# Audio.net
KiCad netlist of a schematic drawn in Altium Designer
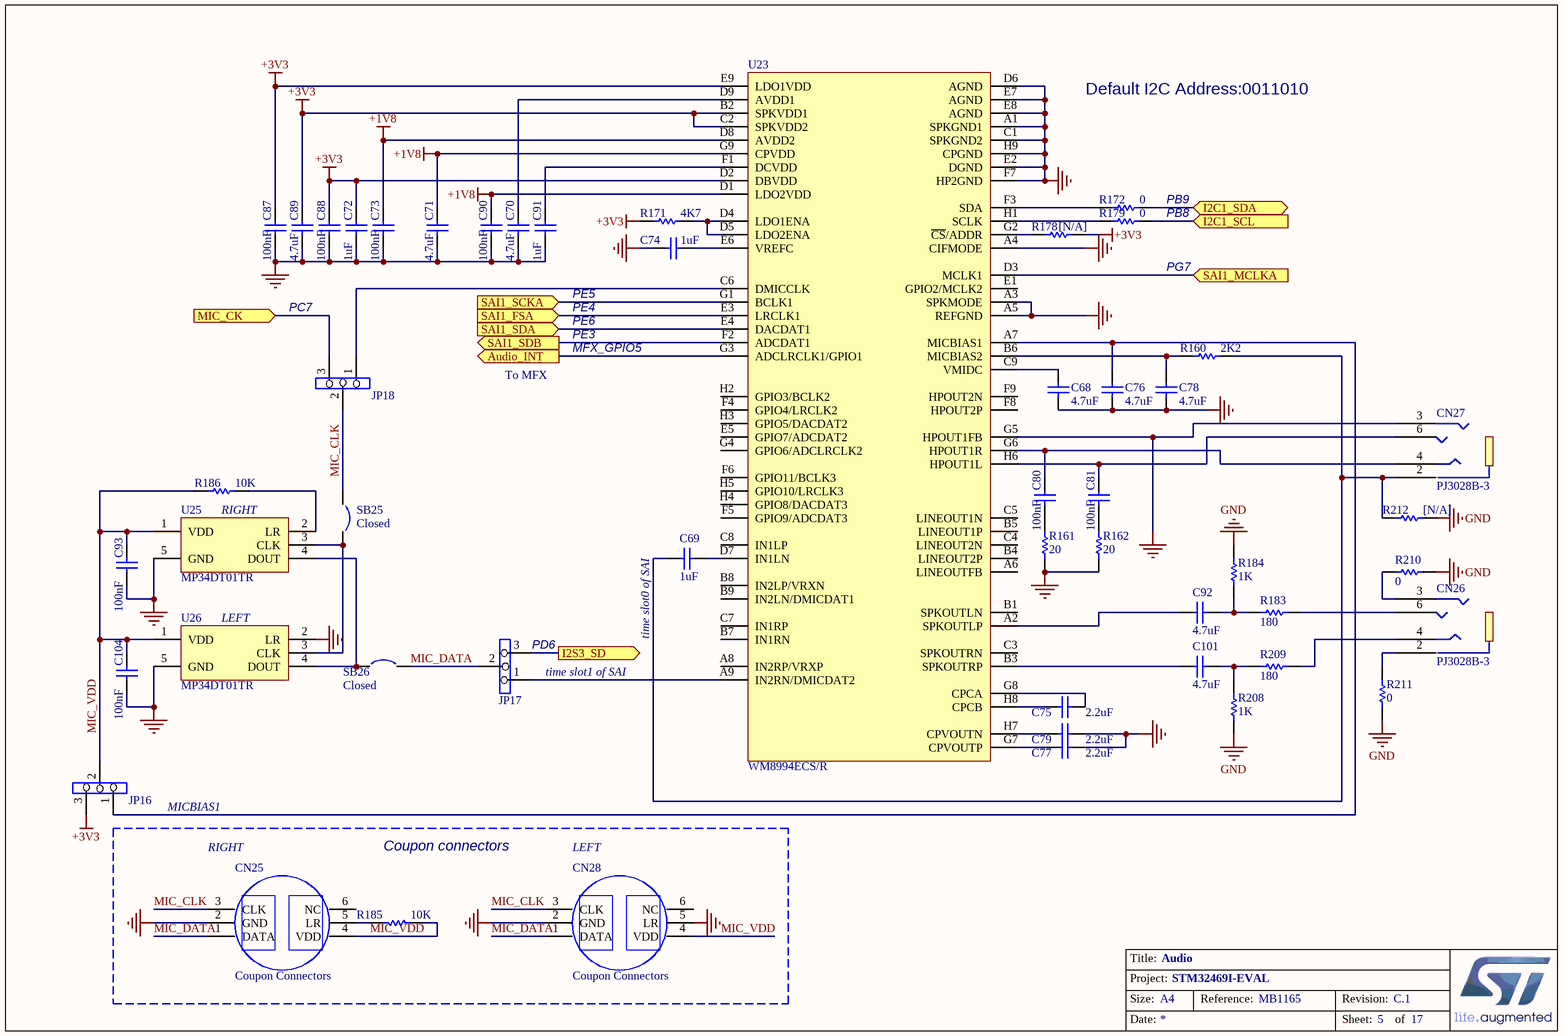
[diagram p0: Audio.SchDoc]

(export (version "E")
  (design (tool "Eeschema 10.0.6"))
  (components
    (comp (ref "C68")
      (value "4.7uF")
      (footprint "0603C")
      (description "Capacitor")
      (fields (field (name "PUBLISHER") "Altium Limited"))
      (libsource (lib "Miscellaneous Devices") (part "Cap"))
    )
    (comp (ref "C69")
      (value "1uF")
      (footprint "0603C")
      (description "Capacitor")
      (fields (field (name "PUBLISHER") "Altium Limited"))
      (libsource (lib "Miscellaneous Devices") (part "CAP"))
    )
    (comp (ref "C70")
      (value "4.7uF")
      (footprint "0603C")
      (description "Capacitor")
      (fields (field (name "PUBLISHER") "Altium Limited"))
      (libsource (lib "Miscellaneous Devices") (part "Cap"))
    )
    (comp (ref "C71")
      (value "4.7uF")
      (footprint "0603C")
      (description "Capacitor")
      (fields (field (name "PUBLISHER") "Altium Limited"))
      (libsource (lib "Miscellaneous Devices") (part "Cap"))
    )
    (comp (ref "C72")
      (value "1uF")
      (footprint "0603C")
      (description "Capacitor")
      (fields (field (name "PUBLISHER") "Altium Limited"))
      (libsource (lib "Miscellaneous Devices") (part "CAP"))
    )
    (comp (ref "C73")
      (value "100nF")
      (footprint "0603C")
      (description "Capacitor")
      (fields (field (name "PUBLISHER") "Altium Limited"))
      (libsource (lib "Miscellaneous Devices") (part "Cap"))
    )
    (comp (ref "C74")
      (value "1uF")
      (footprint "0603C")
      (description "Capacitor")
      (fields (field (name "PUBLISHER") "Altium Limited"))
      (libsource (lib "Miscellaneous Devices") (part "CAP"))
    )
    (comp (ref "C75")
      (value "2.2uF")
      (footprint "0603C")
      (description "Capacitor")
      (fields (field (name "PUBLISHER") "Altium Limited"))
      (libsource (lib "Miscellaneous Devices") (part "CAP"))
    )
    (comp (ref "C76")
      (value "4.7uF")
      (footprint "0603C")
      (description "Capacitor")
      (fields (field (name "PUBLISHER") "Altium Limited"))
      (libsource (lib "Miscellaneous Devices") (part "Cap"))
    )
    (comp (ref "C77")
      (value "2.2uF")
      (footprint "0603C")
      (description "Capacitor")
      (fields (field (name "PUBLISHER") "Altium Limited"))
      (libsource (lib "Miscellaneous Devices") (part "CAP"))
    )
    (comp (ref "C78")
      (value "4.7uF")
      (footprint "0603C")
      (description "Capacitor")
      (fields (field (name "PUBLISHER") "Altium Limited"))
      (libsource (lib "Miscellaneous Devices") (part "Cap"))
    )
    (comp (ref "C79")
      (value "2.2uF")
      (footprint "0603C")
      (description "Capacitor")
      (fields (field (name "PUBLISHER") "Altium Limited"))
      (libsource (lib "Miscellaneous Devices") (part "CAP"))
    )
    (comp (ref "C80")
      (value "100nF")
      (footprint "0603C")
      (description "Capacitor")
      (fields (field (name "PUBLISHER") "Altium Limited"))
      (libsource (lib "Miscellaneous Devices") (part "Cap"))
    )
    (comp (ref "C81")
      (value "100nF")
      (footprint "0603C")
      (description "Capacitor")
      (fields (field (name "PUBLISHER") "Altium Limited"))
      (libsource (lib "Miscellaneous Devices") (part "Cap"))
    )
    (comp (ref "C87")
      (value "100nF")
      (footprint "0603C")
      (description "Capacitor")
      (fields (field (name "PUBLISHER") "Altium Limited"))
      (libsource (lib "Miscellaneous Devices") (part "Cap"))
    )
    (comp (ref "C88")
      (value "100nF")
      (footprint "0603C")
      (description "Capacitor")
      (fields (field (name "PUBLISHER") "Altium Limited"))
      (libsource (lib "Miscellaneous Devices") (part "Cap"))
    )
    (comp (ref "C89")
      (value "4.7uF")
      (footprint "0603C")
      (description "Capacitor")
      (fields (field (name "PUBLISHER") "Altium Limited"))
      (libsource (lib "Miscellaneous Devices") (part "Cap"))
    )
    (comp (ref "C90")
      (value "100nF")
      (footprint "0603C")
      (description "Capacitor")
      (fields (field (name "PUBLISHER") "Altium Limited"))
      (libsource (lib "Miscellaneous Devices") (part "Cap"))
    )
    (comp (ref "C91")
      (value "1uF")
      (footprint "0603C")
      (description "Capacitor")
      (fields (field (name "PUBLISHER") "Altium Limited"))
      (libsource (lib "Miscellaneous Devices") (part "CAP"))
    )
    (comp (ref "C92")
      (value "4.7uF")
      (footprint "0603C")
      (description "Capacitor")
      (fields (field (name "PUBLISHER") "Altium Limited"))
      (libsource (lib "Miscellaneous Devices") (part "Cap"))
    )
    (comp (ref "C93")
      (value "100nF")
      (footprint "0603C")
      (description "Capacitor")
      (fields (field (name "PUBLISHER") "Altium Limited"))
      (libsource (lib "Miscellaneous Devices") (part "Cap"))
    )
    (comp (ref "C101")
      (value "4.7uF")
      (footprint "0603C")
      (description "Capacitor")
      (fields (field (name "PUBLISHER") "Altium Limited"))
      (libsource (lib "Miscellaneous Devices") (part "Cap"))
    )
    (comp (ref "C104")
      (value "100nF")
      (footprint "0603C")
      (description "Capacitor")
      (fields (field (name "PUBLISHER") "Altium Limited"))
      (libsource (lib "Miscellaneous Devices") (part "Cap"))
    )
    (comp (ref "CN25")
      (value "Coupon Connectors")
      (footprint "Coupon")
      (description "Header, 3-Pin, Single row")
      (fields (field (name "PUBLISHER") "Altium Limited"))
      (libsource (lib "MB1167") (part "Coupon Connectors"))
    )
    (comp (ref "CN26") (value "PJ3028B-3") (footprint "PJ3028B") (libsource (lib "MB786") (part "PJ3028B-3")))
    (comp (ref "CN27") (value "PJ3028B-3") (footprint "PJ3028B") (libsource (lib "MB786") (part "PJ3028B-3")))
    (comp (ref "CN28")
      (value "Coupon Connectors")
      (footprint "Coupon")
      (description "Header, 3-Pin, Single row")
      (fields (field (name "PUBLISHER") "Altium Limited"))
      (libsource (lib "MB1167") (part "Coupon Connectors"))
    )
    (comp (ref "JP16") (value "~") (footprint "SIP3") (libsource (lib "STR910_SCHLIB") (part "Jumper3")))
    (comp (ref "JP17") (value "~") (footprint "SIP3") (libsource (lib "STR910_SCHLIB") (part "Jumper3")))
    (comp (ref "JP18") (value "~") (footprint "SIP3") (libsource (lib "STR910_SCHLIB") (part "Jumper3")))
    (comp (ref "R160")
      (value "2K2")
      (footprint "0603R")
      (description "Resistor")
      (fields (field (name "PUBLISHER") "Altium Limited"))
      (libsource (lib "Miscellaneous Devices") (part "Res1"))
    )
    (comp (ref "R161")
      (value "20")
      (footprint "0603R")
      (description "Resistor")
      (fields (field (name "PUBLISHER") "Altium Limited"))
      (libsource (lib "Miscellaneous Devices") (part "Res1"))
    )
    (comp (ref "R162")
      (value "20")
      (footprint "0603R")
      (description "Resistor")
      (fields (field (name "PUBLISHER") "Altium Limited"))
      (libsource (lib "Miscellaneous Devices") (part "Res1"))
    )
    (comp (ref "R171")
      (value "4K7")
      (footprint "0603R")
      (description "Resistor")
      (fields (field (name "PUBLISHER") "Altium Limited"))
      (libsource (lib "Miscellaneous Devices") (part "Res1"))
    )
    (comp (ref "R172")
      (value "0")
      (footprint "0603R")
      (description "Resistor")
      (fields (field (name "PUBLISHER") "Altium Limited"))
      (libsource (lib "Miscellaneous Devices") (part "Res1"))
    )
    (comp (ref "R178")
      (value "[N/A]")
      (footprint "0603R")
      (description "Resistor")
      (fields (field (name "PUBLISHER") "Altium Limited"))
      (libsource (lib "Miscellaneous Devices") (part "Res1"))
    )
    (comp (ref "R179")
      (value "0")
      (footprint "0603R")
      (description "Resistor")
      (fields (field (name "PUBLISHER") "Altium Limited"))
      (libsource (lib "Miscellaneous Devices") (part "Res1"))
    )
    (comp (ref "R183")
      (value "180")
      (footprint "0402R")
      (description "Resistor")
      (fields (field (name "PUBLISHER") "Altium Limited"))
      (libsource (lib "Miscellaneous Devices") (part "Res1"))
    )
    (comp (ref "R184")
      (value "1K")
      (footprint "0402R")
      (description "Resistor")
      (fields (field (name "PUBLISHER") "Altium Limited"))
      (libsource (lib "Miscellaneous Devices") (part "Res1"))
    )
    (comp (ref "R185")
      (value "10K")
      (footprint "0603R")
      (description "Resistor")
      (fields (field (name "PUBLISHER") "Altium Limited"))
      (libsource (lib "Miscellaneous Devices") (part "Res1"))
    )
    (comp (ref "R186")
      (value "10K")
      (footprint "0603R")
      (description "Resistor")
      (fields (field (name "PUBLISHER") "Altium Limited"))
      (libsource (lib "Miscellaneous Devices") (part "Res1"))
    )
    (comp (ref "R208")
      (value "1K")
      (footprint "0402R")
      (description "Resistor")
      (fields (field (name "PUBLISHER") "Altium Limited"))
      (libsource (lib "Miscellaneous Devices") (part "Res1"))
    )
    (comp (ref "R209")
      (value "180")
      (footprint "0402R")
      (description "Resistor")
      (fields (field (name "PUBLISHER") "Altium Limited"))
      (libsource (lib "Miscellaneous Devices") (part "Res1"))
    )
    (comp (ref "R210")
      (value "0")
      (footprint "0603R")
      (description "Resistor")
      (fields (field (name "PUBLISHER") "Altium Limited"))
      (libsource (lib "Miscellaneous Devices") (part "Res1"))
    )
    (comp (ref "R211")
      (value "0")
      (footprint "0603R")
      (description "Resistor")
      (fields (field (name "PUBLISHER") "Altium Limited"))
      (libsource (lib "Miscellaneous Devices") (part "Res1"))
    )
    (comp (ref "R212")
      (value "[N/A]")
      (footprint "0603R")
      (description "Resistor")
      (fields (field (name "PUBLISHER") "Altium Limited"))
      (libsource (lib "Miscellaneous Devices") (part "Res1"))
    )
    (comp (ref "SB25")
      (value "Closed")
      (footprint "SB_0603")
      (description "Circuit Breaker")
      (fields (field (name "PUBLISHER") "Altium Limited"))
      (libsource (lib "MB1165") (part "Circuit Breaker_close"))
    )
    (comp (ref "SB26")
      (value "Closed")
      (footprint "SB_0603")
      (description "Circuit Breaker")
      (fields (field (name "PUBLISHER") "Altium Limited"))
      (libsource (lib "MB1165") (part "Circuit Breaker_close"))
    )
    (comp (ref "U23")
      (value "WM8994ECS/R")
      (footprint "BGA72_0R5_4R5X4")
      (libsource (lib "mb1045") (part "WM8994ECS/R"))
    )
    (comp (ref "U25")
      (value "MP34DT01TR")
      (footprint "MP34DT01TR")
      (description "MEMS audio sensor")
      (fields (field (name "PUBLISHER") "Altium Limited"))
      (libsource (lib "mb1045") (part "MP34DT01TR"))
    )
    (comp (ref "U26")
      (value "MP34DT01TR")
      (footprint "MP34DT01TR")
      (description "MEMS audio sensor")
      (fields (field (name "PUBLISHER") "Altium Limited"))
      (libsource (lib "mb1045") (part "MP34DT01TR"))
    )
  )
  (nets
    (net (code "1") (name "+1V8") (class "Default")
      (node (ref "C71") (pin "1") (pinfunction "1_1") (pintype "passive"))
      (node (ref "C73") (pin "1") (pinfunction "1_1") (pintype "passive"))
      (node (ref "C90") (pin "1") (pinfunction "1_1") (pintype "passive"))
      (node (ref "U23") (pin "D1") (pinfunction "LDO2VDD_D1") (pintype "passive"))
      (node (ref "U23") (pin "D8") (pinfunction "AVDD2_D8") (pintype "passive"))
      (node (ref "U23") (pin "G9") (pinfunction "CPVDD_G9") (pintype "passive"))
    )
    (net (code "2") (name "+3V3") (class "Default")
      (node (ref "C72") (pin "1") (pinfunction "1_1") (pintype "passive"))
      (node (ref "C87") (pin "1") (pinfunction "1_1") (pintype "passive"))
      (node (ref "C88") (pin "1") (pinfunction "1_1") (pintype "passive"))
      (node (ref "C89") (pin "1") (pinfunction "1_1") (pintype "passive"))
      (node (ref "JP16") (pin "3") (pintype "passive"))
      (node (ref "R171") (pin "2") (pinfunction "2_2") (pintype "passive"))
      (node (ref "R178") (pin "1") (pinfunction "1_1") (pintype "passive"))
      (node (ref "U23") (pin "B2") (pinfunction "SPKVDD1_B2") (pintype "passive"))
      (node (ref "U23") (pin "C2") (pinfunction "SPKVDD2_C2") (pintype "passive"))
      (node (ref "U23") (pin "D2") (pinfunction "DBVDD_D2") (pintype "passive"))
      (node (ref "U23") (pin "E9") (pinfunction "LDO1VDD_E9") (pintype "passive"))
    )
    (net (code "3") (name "/Audio_INT") (class "Default")
      (node (ref "U23") (pin "G3") (pinfunction "ADCLRCLK1/GPIO1_G3") (pintype "passive"))
    )
    (net (code "4") (name "/I2C1_SCL") (class "Default")
      (node (ref "R179") (pin "1") (pinfunction "1_1") (pintype "passive"))
    )
    (net (code "5") (name "/I2C1_SDA") (class "Default")
      (node (ref "R172") (pin "1") (pinfunction "1_1") (pintype "passive"))
    )
    (net (code "6") (name "/I2S3_SD") (class "Default") (node (ref "JP17") (pin "3") (pintype "passive")))
    (net (code "7") (name "/MIC_CK") (class "Default") (node (ref "JP18") (pin "3") (pintype "passive")))
    (net (code "8") (name "/MIC_CLK") (class "Default")
      (node (ref "CN25") (pin "3") (pinfunction "CLK_3") (pintype "passive"))
      (node (ref "CN28") (pin "3") (pinfunction "CLK_3") (pintype "passive"))
      (node (ref "JP18") (pin "2") (pintype "passive"))
      (node (ref "SB25") (pin "1") (pinfunction "1_1") (pintype "passive"))
    )
    (net (code "9") (name "/MIC_DATA") (class "Default")
      (node (ref "CN25") (pin "1") (pinfunction "DATA_1") (pintype "passive"))
      (node (ref "CN28") (pin "1") (pinfunction "DATA_1") (pintype "passive"))
      (node (ref "JP17") (pin "2") (pintype "passive"))
      (node (ref "SB26") (pin "2") (pinfunction "2_2") (pintype "passive"))
    )
    (net (code "10") (name "/MIC_VDD") (class "Default")
      (node (ref "C104") (pin "1") (pinfunction "1_1") (pintype "passive"))
      (node (ref "C93") (pin "1") (pinfunction "1_1") (pintype "passive"))
      (node (ref "CN25") (pin "4") (pinfunction "VDD_4") (pintype "passive"))
      (node (ref "CN28") (pin "4") (pinfunction "VDD_4") (pintype "passive"))
      (node (ref "JP16") (pin "2") (pintype "passive"))
      (node (ref "R185") (pin "2") (pinfunction "2_2") (pintype "passive"))
      (node (ref "R186") (pin "2") (pinfunction "2_2") (pintype "passive"))
      (node (ref "U25") (pin "1") (pinfunction "VDD_1") (pintype "passive"))
      (node (ref "U26") (pin "1") (pinfunction "VDD_1") (pintype "passive"))
    )
    (net (code "11") (name "/SAI1_FSA") (class "Default")
      (node (ref "U23") (pin "E3") (pinfunction "LRCLK1_E3") (pintype "passive"))
    )
    (net (code "12") (name "/SAI1_MCLKA") (class "Default")
      (node (ref "U23") (pin "D3") (pinfunction "MCLK1_D3") (pintype "passive"))
    )
    (net (code "13") (name "/SAI1_SCKA") (class "Default")
      (node (ref "U23") (pin "G1") (pinfunction "BCLK1_G1") (pintype "passive"))
    )
    (net (code "14") (name "/SAI1_SDA") (class "Default")
      (node (ref "U23") (pin "E4") (pinfunction "DACDAT1_E4") (pintype "passive"))
    )
    (net (code "15") (name "/SAI1_SDB") (class "Default")
      (node (ref "U23") (pin "F2") (pinfunction "ADCDAT1_F2") (pintype "passive"))
    )
    (net (code "16") (name "GND") (class "Default")
      (node (ref "C104") (pin "2") (pinfunction "2_2") (pintype "passive"))
      (node (ref "C68") (pin "1") (pinfunction "1_1") (pintype "passive"))
      (node (ref "C70") (pin "2") (pinfunction "2_2") (pintype "passive"))
      (node (ref "C71") (pin "2") (pinfunction "2_2") (pintype "passive"))
      (node (ref "C72") (pin "2") (pinfunction "2_2") (pintype "passive"))
      (node (ref "C73") (pin "2") (pinfunction "2_2") (pintype "passive"))
      (node (ref "C74") (pin "2") (pinfunction "2_2") (pintype "passive"))
      (node (ref "C76") (pin "1") (pinfunction "1_1") (pintype "passive"))
      (node (ref "C77") (pin "2") (pinfunction "2_2") (pintype "passive"))
      (node (ref "C78") (pin "1") (pinfunction "1_1") (pintype "passive"))
      (node (ref "C79") (pin "2") (pinfunction "2_2") (pintype "passive"))
      (node (ref "C87") (pin "2") (pinfunction "2_2") (pintype "passive"))
      (node (ref "C88") (pin "2") (pinfunction "2_2") (pintype "passive"))
      (node (ref "C89") (pin "2") (pinfunction "2_2") (pintype "passive"))
      (node (ref "C90") (pin "2") (pinfunction "2_2") (pintype "passive"))
      (node (ref "C91") (pin "2") (pinfunction "2_2") (pintype "passive"))
      (node (ref "C93") (pin "2") (pinfunction "2_2") (pintype "passive"))
      (node (ref "CN25") (pin "2") (pinfunction "GND_2") (pintype "passive"))
      (node (ref "CN27") (pin "3") (pintype "passive"))
      (node (ref "CN28") (pin "2") (pinfunction "GND_2") (pintype "passive"))
      (node (ref "CN28") (pin "5") (pinfunction "LR_5") (pintype "passive"))
      (node (ref "R161") (pin "2") (pinfunction "2_2") (pintype "passive"))
      (node (ref "R162") (pin "2") (pinfunction "2_2") (pintype "passive"))
      (node (ref "R184") (pin "2") (pinfunction "2_2") (pintype "passive"))
      (node (ref "R208") (pin "1") (pinfunction "1_1") (pintype "passive"))
      (node (ref "R210") (pin "2") (pinfunction "2_2") (pintype "passive"))
      (node (ref "R211") (pin "2") (pinfunction "2_2") (pintype "passive"))
      (node (ref "R212") (pin "1") (pinfunction "1_1") (pintype "passive"))
      (node (ref "U23") (pin "A1") (pinfunction "SPKGND1_A1") (pintype "passive"))
      (node (ref "U23") (pin "A3") (pinfunction "SPKMODE_A3") (pintype "passive"))
      (node (ref "U23") (pin "A4") (pinfunction "CIFMODE_A4") (pintype "passive"))
      (node (ref "U23") (pin "A5") (pinfunction "REFGND_A5") (pintype "passive"))
      (node (ref "U23") (pin "C1") (pinfunction "SPKGND2_C1") (pintype "passive"))
      (node (ref "U23") (pin "D6") (pinfunction "AGND_D6") (pintype "passive"))
      (node (ref "U23") (pin "E2") (pinfunction "DGND_E2") (pintype "passive"))
      (node (ref "U23") (pin "E7") (pinfunction "AGND_E7") (pintype "passive"))
      (node (ref "U23") (pin "E8") (pinfunction "AGND_E8") (pintype "passive"))
      (node (ref "U23") (pin "F7") (pinfunction "HP2GND_F7") (pintype "passive"))
      (node (ref "U23") (pin "G5") (pinfunction "HPOUT1FB_G5") (pintype "passive"))
      (node (ref "U23") (pin "H9") (pinfunction "CPGND_H9") (pintype "passive"))
      (node (ref "U25") (pin "5") (pinfunction "GND_5") (pintype "passive"))
      (node (ref "U26") (pin "2") (pinfunction "LR_2") (pintype "passive"))
      (node (ref "U26") (pin "5") (pinfunction "GND_5") (pintype "passive"))
    )
    (net (code "17") (name "Net-(C69-Pad2)") (class "Default")
      (node (ref "C69") (pin "2") (pinfunction "2_2") (pintype "passive"))
      (node (ref "CN27") (pin "2") (pintype "passive"))
      (node (ref "R160") (pin "1") (pinfunction "1_1") (pintype "passive"))
      (node (ref "R212") (pin "2") (pinfunction "2_2") (pintype "passive"))
    )
    (net (code "18") (name "Net-(C80-Pad2)") (class "Default")
      (node (ref "C80") (pin "2") (pinfunction "2_2") (pintype "passive"))
      (node (ref "R161") (pin "1") (pinfunction "1_1") (pintype "passive"))
    )
    (net (code "19") (name "Net-(C81-Pad2)") (class "Default")
      (node (ref "C81") (pin "2") (pinfunction "2_2") (pintype "passive"))
      (node (ref "R162") (pin "1") (pinfunction "1_1") (pintype "passive"))
    )
    (net (code "20") (name "Net-(C92-Pad1)") (class "Default")
      (node (ref "C92") (pin "1") (pinfunction "1_1") (pintype "passive"))
      (node (ref "R183") (pin "1") (pinfunction "1_1") (pintype "passive"))
      (node (ref "R184") (pin "1") (pinfunction "1_1") (pintype "passive"))
    )
    (net (code "21") (name "Net-(C101-Pad1)") (class "Default")
      (node (ref "C101") (pin "1") (pinfunction "1_1") (pintype "passive"))
      (node (ref "R208") (pin "2") (pinfunction "2_2") (pintype "passive"))
      (node (ref "R209") (pin "2") (pinfunction "2_2") (pintype "passive"))
    )
    (net (code "22") (name "Net-(CN25-LR)") (class "Default")
      (node (ref "CN25") (pin "5") (pinfunction "LR_5") (pintype "passive"))
      (node (ref "R185") (pin "1") (pinfunction "1_1") (pintype "passive"))
    )
    (net (code "23") (name "Net-(CN26-Pad2)") (class "Default")
      (node (ref "CN26") (pin "2") (pintype "passive"))
      (node (ref "R211") (pin "1") (pinfunction "1_1") (pintype "passive"))
    )
    (net (code "24") (name "Net-(CN26-Pad3)") (class "Default")
      (node (ref "CN26") (pin "3") (pintype "passive"))
      (node (ref "R210") (pin "1") (pinfunction "1_1") (pintype "passive"))
    )
    (net (code "25") (name "Net-(CN26-Pad4)") (class "Default")
      (node (ref "CN26") (pin "4") (pintype "passive"))
      (node (ref "R209") (pin "1") (pinfunction "1_1") (pintype "passive"))
    )
    (net (code "26") (name "Net-(CN26-Pad6)") (class "Default")
      (node (ref "CN26") (pin "6") (pintype "passive"))
      (node (ref "R183") (pin "2") (pinfunction "2_2") (pintype "passive"))
    )
    (net (code "27") (name "Net-(U23-AVDD1)") (class "Default")
      (node (ref "C70") (pin "1") (pinfunction "1_1") (pintype "passive"))
      (node (ref "U23") (pin "D9") (pinfunction "AVDD1_D9") (pintype "passive"))
    )
    (net (code "28") (name "Net-(U23-CPCA)") (class "Default")
      (node (ref "C75") (pin "2") (pinfunction "2_2") (pintype "passive"))
      (node (ref "U23") (pin "G8") (pinfunction "CPCA_G8") (pintype "passive"))
    )
    (net (code "29") (name "Net-(U23-CPCB)") (class "Default")
      (node (ref "C75") (pin "1") (pinfunction "1_1") (pintype "passive"))
      (node (ref "U23") (pin "H8") (pinfunction "CPCB_H8") (pintype "passive"))
    )
    (net (code "30") (name "Net-(U23-CPVOUTN)") (class "Default")
      (node (ref "C79") (pin "1") (pinfunction "1_1") (pintype "passive"))
      (node (ref "U23") (pin "H7") (pinfunction "CPVOUTN_H7") (pintype "passive"))
    )
    (net (code "31") (name "Net-(U23-CPVOUTP)") (class "Default")
      (node (ref "C77") (pin "1") (pinfunction "1_1") (pintype "passive"))
      (node (ref "U23") (pin "G7") (pinfunction "CPVOUTP_G7") (pintype "passive"))
    )
    (net (code "32") (name "Net-(U23-DCVDD)") (class "Default")
      (node (ref "C91") (pin "1") (pinfunction "1_1") (pintype "passive"))
      (node (ref "U23") (pin "F1") (pinfunction "DCVDD_F1") (pintype "passive"))
    )
    (net (code "33") (name "Net-(U23-DMICCLK)") (class "Default")
      (node (ref "JP18") (pin "1") (pintype "passive"))
      (node (ref "U23") (pin "C6") (pinfunction "DMICCLK_C6") (pintype "passive"))
    )
    (net (code "34") (name "Net-(U23-HPOUT1L)") (class "Default")
      (node (ref "C81") (pin "1") (pinfunction "1_1") (pintype "passive"))
      (node (ref "CN27") (pin "6") (pintype "passive"))
      (node (ref "U23") (pin "H6") (pinfunction "HPOUT1L_H6") (pintype "passive"))
    )
    (net (code "35") (name "Net-(U23-HPOUT1R)") (class "Default")
      (node (ref "C80") (pin "1") (pinfunction "1_1") (pintype "passive"))
      (node (ref "CN27") (pin "4") (pintype "passive"))
      (node (ref "U23") (pin "G6") (pinfunction "HPOUT1R_G6") (pintype "passive"))
    )
    (net (code "36") (name "Net-(U23-IN1LN)") (class "Default")
      (node (ref "C69") (pin "1") (pinfunction "1_1") (pintype "passive"))
      (node (ref "U23") (pin "D7") (pinfunction "IN1LN_D7") (pintype "passive"))
    )
    (net (code "37") (name "Net-(U23-IN2RN{slash}DMICDAT2)") (class "Default")
      (node (ref "JP17") (pin "1") (pintype "passive"))
      (node (ref "U23") (pin "A9") (pinfunction "IN2RN/DMICDAT2_A9") (pintype "passive"))
    )
    (net (code "38") (name "Net-(U23-LDO1ENA)") (class "Default")
      (node (ref "R171") (pin "1") (pinfunction "1_1") (pintype "passive"))
      (node (ref "U23") (pin "D4") (pinfunction "LDO1ENA_D4") (pintype "passive"))
      (node (ref "U23") (pin "D5") (pinfunction "LDO2ENA_D5") (pintype "passive"))
    )
    (net (code "39") (name "Net-(U23-MICBIAS1)") (class "Default")
      (node (ref "C76") (pin "2") (pinfunction "2_2") (pintype "passive"))
      (node (ref "JP16") (pin "1") (pintype "passive"))
      (node (ref "U23") (pin "A7") (pinfunction "MICBIAS1_A7") (pintype "passive"))
    )
    (net (code "40") (name "Net-(U23-MICBIAS2)") (class "Default")
      (node (ref "C78") (pin "2") (pinfunction "2_2") (pintype "passive"))
      (node (ref "R160") (pin "2") (pinfunction "2_2") (pintype "passive"))
      (node (ref "U23") (pin "B6") (pinfunction "MICBIAS2_B6") (pintype "passive"))
    )
    (net (code "41") (name "Net-(U23-SCLK)") (class "Default")
      (node (ref "R179") (pin "2") (pinfunction "2_2") (pintype "passive"))
      (node (ref "U23") (pin "H1") (pinfunction "SCLK_H1") (pintype "passive"))
    )
    (net (code "42") (name "Net-(U23-SDA)") (class "Default")
      (node (ref "R172") (pin "2") (pinfunction "2_2") (pintype "passive"))
      (node (ref "U23") (pin "F3") (pinfunction "SDA_F3") (pintype "passive"))
    )
    (net (code "43") (name "Net-(U23-SPKOUTLP)") (class "Default")
      (node (ref "C92") (pin "2") (pinfunction "2_2") (pintype "passive"))
      (node (ref "U23") (pin "A2") (pinfunction "SPKOUTLP_A2") (pintype "passive"))
    )
    (net (code "44") (name "Net-(U23-SPKOUTRP)") (class "Default")
      (node (ref "C101") (pin "2") (pinfunction "2_2") (pintype "passive"))
      (node (ref "U23") (pin "B3") (pinfunction "SPKOUTRP_B3") (pintype "passive"))
    )
    (net (code "45") (name "Net-(U23-VMIDC)") (class "Default")
      (node (ref "C68") (pin "2") (pinfunction "2_2") (pintype "passive"))
      (node (ref "U23") (pin "C9") (pinfunction "VMIDC_C9") (pintype "passive"))
    )
    (net (code "46") (name "Net-(U23-VREFC)") (class "Default")
      (node (ref "C74") (pin "1") (pinfunction "1_1") (pintype "passive"))
      (node (ref "U23") (pin "E6") (pinfunction "VREFC_E6") (pintype "passive"))
    )
    (net (code "47") (name "Net-(U23-~{CS}{slash}ADDR)") (class "Default")
      (node (ref "R178") (pin "2") (pinfunction "2_2") (pintype "passive"))
      (node (ref "U23") (pin "G2") (pinfunction "~{CS}/ADDR_G2") (pintype "passive"))
    )
    (net (code "48") (name "Net-(U25-CLK)") (class "Default")
      (node (ref "SB25") (pin "2") (pinfunction "2_2") (pintype "passive"))
      (node (ref "U25") (pin "3") (pinfunction "CLK_3") (pintype "passive"))
      (node (ref "U26") (pin "3") (pinfunction "CLK_3") (pintype "passive"))
    )
    (net (code "49") (name "Net-(U25-DOUT)") (class "Default")
      (node (ref "SB26") (pin "1") (pinfunction "1_1") (pintype "passive"))
      (node (ref "U25") (pin "4") (pinfunction "DOUT_4") (pintype "passive"))
      (node (ref "U26") (pin "4") (pinfunction "DOUT_4") (pintype "passive"))
    )
    (net (code "50") (name "Net-(U25-LR)") (class "Default")
      (node (ref "R186") (pin "1") (pinfunction "1_1") (pintype "passive"))
      (node (ref "U25") (pin "2") (pinfunction "LR_2") (pintype "passive"))
    )
    (net (code "51") (name "unconnected-(CN25-NC-Pad6)") (class "Default")
      (node (ref "CN25") (pin "6") (pinfunction "NC_6") (pintype "passive"))
    )
    (net (code "52") (name "unconnected-(CN28-NC-Pad6)") (class "Default")
      (node (ref "CN28") (pin "6") (pinfunction "NC_6") (pintype "passive"))
    )
    (net (code "53") (name "unconnected-(U23-GPIO2{slash}MCLK2-PadE1)") (class "Default")
      (node (ref "U23") (pin "E1") (pinfunction "GPIO2/MCLK2_E1") (pintype "passive"))
    )
    (net (code "54") (name "unconnected-(U23-GPIO3{slash}BCLK2-PadH2)") (class "Default")
      (node (ref "U23") (pin "H2") (pinfunction "GPIO3/BCLK2_H2") (pintype "passive"))
    )
    (net (code "55") (name "unconnected-(U23-GPIO4{slash}LRCLK2-PadF4)") (class "Default")
      (node (ref "U23") (pin "F4") (pinfunction "GPIO4/LRCLK2_F4") (pintype "passive"))
    )
    (net (code "56") (name "unconnected-(U23-GPIO5{slash}DACDAT2-PadH3)") (class "Default")
      (node (ref "U23") (pin "H3") (pinfunction "GPIO5/DACDAT2_H3") (pintype "passive"))
    )
    (net (code "57") (name "unconnected-(U23-GPIO6{slash}ADCLRCLK2-PadG4)") (class "Default")
      (node (ref "U23") (pin "G4") (pinfunction "GPIO6/ADCLRCLK2_G4") (pintype "passive"))
    )
    (net (code "58") (name "unconnected-(U23-GPIO7{slash}ADCDAT2-PadE5)") (class "Default")
      (node (ref "U23") (pin "E5") (pinfunction "GPIO7/ADCDAT2_E5") (pintype "passive"))
    )
    (net (code "59") (name "unconnected-(U23-GPIO8{slash}DACDAT3-PadH4)") (class "Default")
      (node (ref "U23") (pin "H4") (pinfunction "GPIO8/DACDAT3_H4") (pintype "passive"))
    )
    (net (code "60") (name "unconnected-(U23-GPIO9{slash}ADCDAT3-PadF5)") (class "Default")
      (node (ref "U23") (pin "F5") (pinfunction "GPIO9/ADCDAT3_F5") (pintype "passive"))
    )
    (net (code "61") (name "unconnected-(U23-GPIO10{slash}LRCLK3-PadH5)") (class "Default")
      (node (ref "U23") (pin "H5") (pinfunction "GPIO10/LRCLK3_H5") (pintype "passive"))
    )
    (net (code "62") (name "unconnected-(U23-GPIO11{slash}BCLK3-PadF6)") (class "Default")
      (node (ref "U23") (pin "F6") (pinfunction "GPIO11/BCLK3_F6") (pintype "passive"))
    )
    (net (code "63") (name "unconnected-(U23-HPOUT2N-PadF9)") (class "Default")
      (node (ref "U23") (pin "F9") (pinfunction "HPOUT2N_F9") (pintype "passive"))
    )
    (net (code "64") (name "unconnected-(U23-HPOUT2P-PadF8)") (class "Default")
      (node (ref "U23") (pin "F8") (pinfunction "HPOUT2P_F8") (pintype "passive"))
    )
    (net (code "65") (name "unconnected-(U23-IN1LP-PadC8)") (class "Default")
      (node (ref "U23") (pin "C8") (pinfunction "IN1LP_C8") (pintype "passive"))
    )
    (net (code "66") (name "unconnected-(U23-IN1RN-PadB7)") (class "Default")
      (node (ref "U23") (pin "B7") (pinfunction "IN1RN_B7") (pintype "passive"))
    )
    (net (code "67") (name "unconnected-(U23-IN1RP-PadC7)") (class "Default")
      (node (ref "U23") (pin "C7") (pinfunction "IN1RP_C7") (pintype "passive"))
    )
    (net (code "68") (name "unconnected-(U23-IN2LN{slash}DMICDAT1-PadB9)") (class "Default")
      (node (ref "U23") (pin "B9") (pinfunction "IN2LN/DMICDAT1_B9") (pintype "passive"))
    )
    (net (code "69") (name "unconnected-(U23-IN2LP{slash}VRXN-PadB8)") (class "Default")
      (node (ref "U23") (pin "B8") (pinfunction "IN2LP/VRXN_B8") (pintype "passive"))
    )
    (net (code "70") (name "unconnected-(U23-IN2RP{slash}VRXP-PadA8)") (class "Default")
      (node (ref "U23") (pin "A8") (pinfunction "IN2RP/VRXP_A8") (pintype "passive"))
    )
    (net (code "71") (name "unconnected-(U23-LINEOUT1N-PadC5)") (class "Default")
      (node (ref "U23") (pin "C5") (pinfunction "LINEOUT1N_C5") (pintype "passive"))
    )
    (net (code "72") (name "unconnected-(U23-LINEOUT1P-PadB5)") (class "Default")
      (node (ref "U23") (pin "B5") (pinfunction "LINEOUT1P_B5") (pintype "passive"))
    )
    (net (code "73") (name "unconnected-(U23-LINEOUT2N-PadC4)") (class "Default")
      (node (ref "U23") (pin "C4") (pinfunction "LINEOUT2N_C4") (pintype "passive"))
    )
    (net (code "74") (name "unconnected-(U23-LINEOUT2P-PadB4)") (class "Default")
      (node (ref "U23") (pin "B4") (pinfunction "LINEOUT2P_B4") (pintype "passive"))
    )
    (net (code "75") (name "unconnected-(U23-LINEOUTFB-PadA6)") (class "Default")
      (node (ref "U23") (pin "A6") (pinfunction "LINEOUTFB_A6") (pintype "passive"))
    )
    (net (code "76") (name "unconnected-(U23-SPKOUTLN-PadB1)") (class "Default")
      (node (ref "U23") (pin "B1") (pinfunction "SPKOUTLN_B1") (pintype "passive"))
    )
    (net (code "77") (name "unconnected-(U23-SPKOUTRN-PadC3)") (class "Default")
      (node (ref "U23") (pin "C3") (pinfunction "SPKOUTRN_C3") (pintype "passive"))
    )
  )
)
